# WOPR_PC.net
KiCad netlist of a schematic drawn in Altium Designer
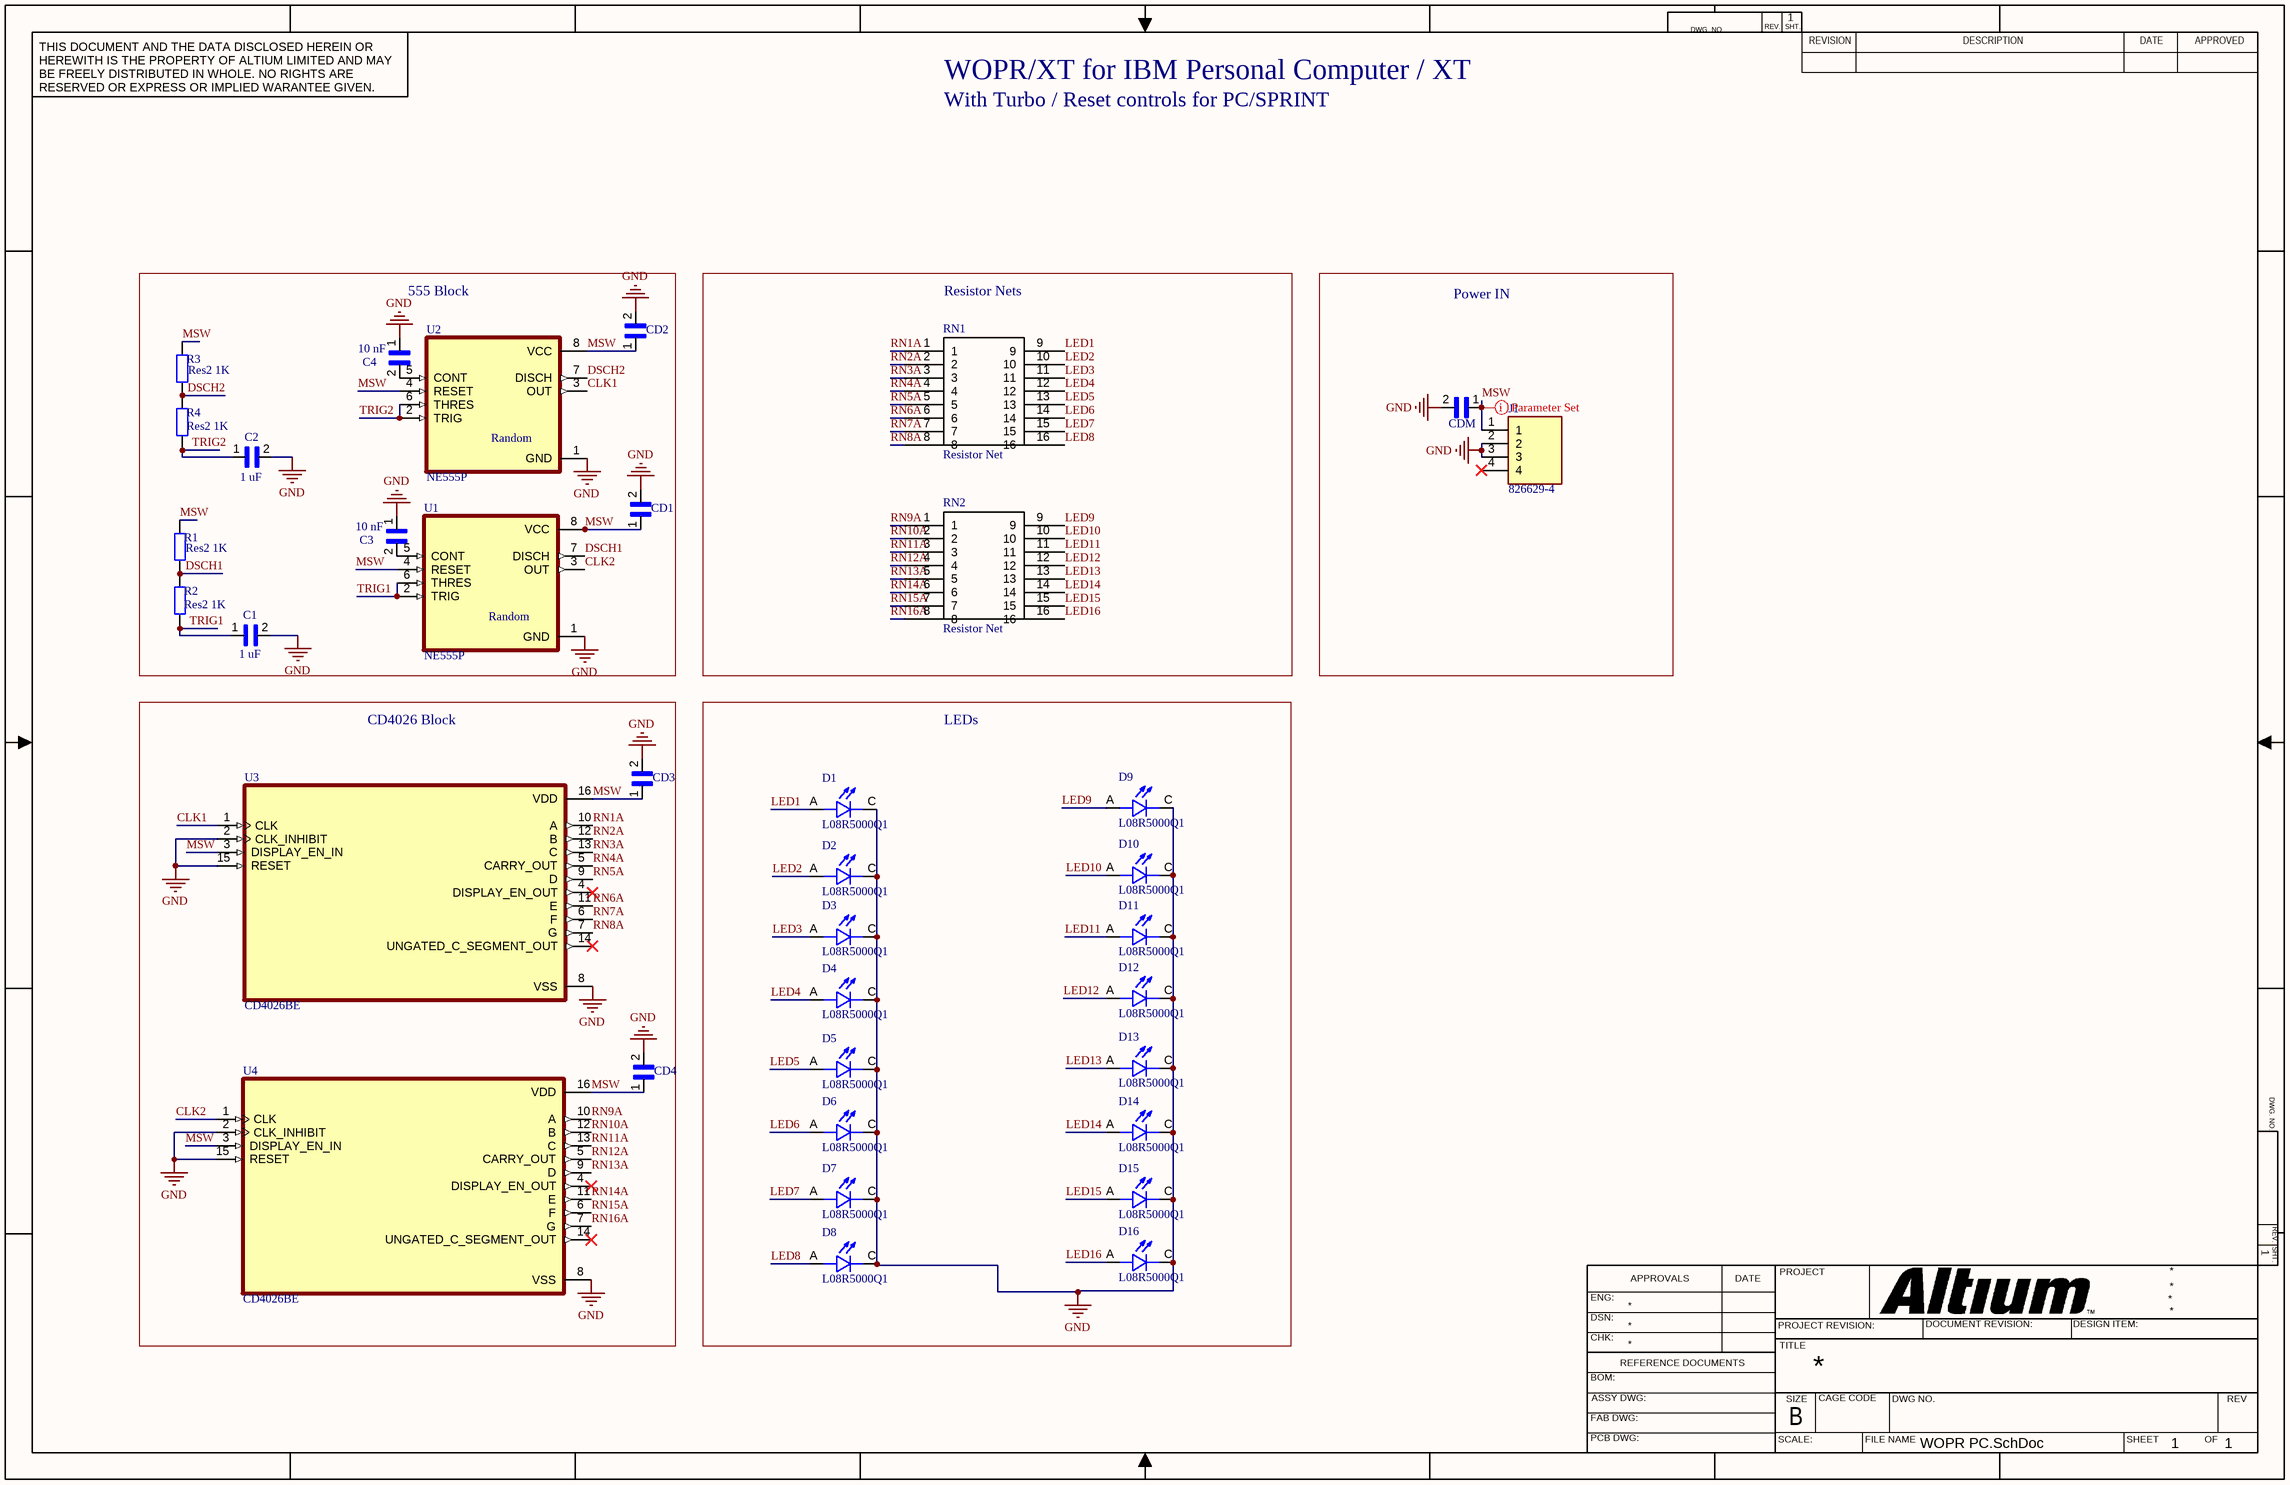
[diagram p0: WOPR PC.SchDoc]

(export (version "E")
  (design (tool "Eeschema 10.0.6"))
  (components
    (comp (ref "C1")
      (value "1 uF")
      (footprint "CAPRB250W50L400T250H550")
      (description "COMMERCIAL GRADE, HALOGEN FREE DIPPED RADIAL / BULK")
      (fields (field (name "MP") "FG18X7R1E105KRT00") (field (name "DIGI-KEY_PART_NUMBER") "445-180204-ND"))
      (libsource (lib "FG18X7R1E105KRT00") (part "FG18X7R1E105KRT00"))
    )
    (comp (ref "C2")
      (value "1 uF")
      (footprint "CAPRB250W50L400T250H550")
      (description "COMMERCIAL GRADE, HALOGEN FREE DIPPED RADIAL / BULK")
      (fields (field (name "MP") "FG18X7R1E105KRT00") (field (name "DIGI-KEY_PART_NUMBER") "445-180204-ND"))
      (libsource (lib "FG18X7R1E105KRT00") (part "FG18X7R1E105KRT00"))
    )
    (comp (ref "C3")
      (value "10 nF")
      (footprint "CAPRB750W60L1450T500H1850")
      (description "Cap Ceramic Single 0.01uF 2000V E -20% to 80% (14.5 X 5mm) Radial Disc 7.5mm 105Â°C Bag")
      (fields (field (name "MP") "CK45E3DD103ZYGNA") (field (name "DIGI-KEY_PART_NUMBER") "445-175346-ND"))
      (libsource (lib "CK45-E3DD103ZYGNA") (part "CK45-E3DD103ZYGNA"))
    )
    (comp (ref "C4")
      (value "10 nF")
      (footprint "CAPRB750W60L1450T500H1850")
      (description "Cap Ceramic Single 0.01uF 2000V E -20% to 80% (14.5 X 5mm) Radial Disc 7.5mm 105Â°C Bag")
      (fields (field (name "MP") "CK45E3DD103ZYGNA") (field (name "DIGI-KEY_PART_NUMBER") "445-175346-ND"))
      (libsource (lib "CK45-E3DD103ZYGNA") (part "CK45-E3DD103ZYGNA"))
    )
    (comp (ref "CD1")
      (value "FG18X7R1H473KNT06")
      (footprint "CAPRB250W50L400T250H550")
      (description "COMMERCIAL GRADE, HALOGEN FREE DIPPED RADIAL / AMMO PACK")
      (fields (field (name "DIGI-KEY_PART_NUMBER") "445-173275-1-ND") (field (name "MF") "TDK"))
      (libsource (lib "FG18X7R1H473KNT06") (part "FG18X7R1H473KNT06"))
    )
    (comp (ref "CD2")
      (value "FG18X7R1H473KNT06")
      (footprint "CAPRB250W50L400T250H550")
      (description "COMMERCIAL GRADE, HALOGEN FREE DIPPED RADIAL / AMMO PACK")
      (fields (field (name "DIGI-KEY_PART_NUMBER") "445-173275-1-ND") (field (name "MF") "TDK"))
      (libsource (lib "FG18X7R1H473KNT06") (part "FG18X7R1H473KNT06"))
    )
    (comp (ref "CD3")
      (value "FG18X7R1H473KNT06")
      (footprint "CAPRB250W50L400T250H550")
      (description "COMMERCIAL GRADE, HALOGEN FREE DIPPED RADIAL / AMMO PACK")
      (fields (field (name "DIGI-KEY_PART_NUMBER") "445-173275-1-ND") (field (name "MF") "TDK"))
      (libsource (lib "FG18X7R1H473KNT06") (part "FG18X7R1H473KNT06"))
    )
    (comp (ref "CD4")
      (value "FG18X7R1H473KNT06")
      (footprint "CAPRB250W50L400T250H550")
      (description "COMMERCIAL GRADE, HALOGEN FREE DIPPED RADIAL / AMMO PACK")
      (fields (field (name "DIGI-KEY_PART_NUMBER") "445-173275-1-ND") (field (name "MF") "TDK"))
      (libsource (lib "FG18X7R1H473KNT06") (part "FG18X7R1H473KNT06"))
    )
    (comp (ref "CDM")
      (value "FG18X7R1H473KNT06")
      (footprint "CAPRB250W50L400T250H550")
      (description "COMMERCIAL GRADE, HALOGEN FREE DIPPED RADIAL / AMMO PACK")
      (fields (field (name "DIGI-KEY_PART_NUMBER") "445-173275-1-ND") (field (name "MF") "TDK"))
      (libsource (lib "") (part "FG18X7R1H473KNT06_1"))
    )
    (comp (ref "D1")
      (value "L08R5000Q1")
      (footprint "LEDRD254W57D500H1070")
      (description "LED, Orange, Through Hole, T-1 3/4 (5mm), 30 mA, 2.1 V, 635 nm")
      (libsource (lib "L08R5000Q1") (part "L08R5000Q1"))
    )
    (comp (ref "D2")
      (value "L08R5000Q1")
      (footprint "LEDRD254W57D500H1070")
      (description "LED, Orange, Through Hole, T-1 3/4 (5mm), 30 mA, 2.1 V, 635 nm")
      (libsource (lib "L08R5000Q1") (part "L08R5000Q1"))
    )
    (comp (ref "D3")
      (value "L08R5000Q1")
      (footprint "LEDRD254W57D500H1070")
      (description "LED, Orange, Through Hole, T-1 3/4 (5mm), 30 mA, 2.1 V, 635 nm")
      (libsource (lib "L08R5000Q1") (part "L08R5000Q1"))
    )
    (comp (ref "D4")
      (value "L08R5000Q1")
      (footprint "LEDRD254W57D500H1070")
      (description "LED, Orange, Through Hole, T-1 3/4 (5mm), 30 mA, 2.1 V, 635 nm")
      (libsource (lib "L08R5000Q1") (part "L08R5000Q1"))
    )
    (comp (ref "D5")
      (value "L08R5000Q1")
      (footprint "LEDRD254W57D500H1070")
      (description "LED, Orange, Through Hole, T-1 3/4 (5mm), 30 mA, 2.1 V, 635 nm")
      (libsource (lib "L08R5000Q1") (part "L08R5000Q1"))
    )
    (comp (ref "D6")
      (value "L08R5000Q1")
      (footprint "LEDRD254W57D500H1070")
      (description "LED, Orange, Through Hole, T-1 3/4 (5mm), 30 mA, 2.1 V, 635 nm")
      (libsource (lib "L08R5000Q1") (part "L08R5000Q1"))
    )
    (comp (ref "D7")
      (value "L08R5000Q1")
      (footprint "LEDRD254W57D500H1070")
      (description "LED, Orange, Through Hole, T-1 3/4 (5mm), 30 mA, 2.1 V, 635 nm")
      (libsource (lib "L08R5000Q1") (part "L08R5000Q1"))
    )
    (comp (ref "D8")
      (value "L08R5000Q1")
      (footprint "LEDRD254W57D500H1070")
      (description "LED, Orange, Through Hole, T-1 3/4 (5mm), 30 mA, 2.1 V, 635 nm")
      (libsource (lib "L08R5000Q1") (part "L08R5000Q1"))
    )
    (comp (ref "D9")
      (value "L08R5000Q1")
      (footprint "LEDRD254W57D500H1070")
      (description "LED, Orange, Through Hole, T-1 3/4 (5mm), 30 mA, 2.1 V, 635 nm")
      (libsource (lib "L08R5000Q1") (part "L08R5000Q1"))
    )
    (comp (ref "D10")
      (value "L08R5000Q1")
      (footprint "LEDRD254W57D500H1070")
      (description "LED, Orange, Through Hole, T-1 3/4 (5mm), 30 mA, 2.1 V, 635 nm")
      (libsource (lib "L08R5000Q1") (part "L08R5000Q1"))
    )
    (comp (ref "D11")
      (value "L08R5000Q1")
      (footprint "LEDRD254W57D500H1070")
      (description "LED, Orange, Through Hole, T-1 3/4 (5mm), 30 mA, 2.1 V, 635 nm")
      (libsource (lib "L08R5000Q1") (part "L08R5000Q1"))
    )
    (comp (ref "D12")
      (value "L08R5000Q1")
      (footprint "LEDRD254W57D500H1070")
      (description "LED, Orange, Through Hole, T-1 3/4 (5mm), 30 mA, 2.1 V, 635 nm")
      (libsource (lib "L08R5000Q1") (part "L08R5000Q1"))
    )
    (comp (ref "D13")
      (value "L08R5000Q1")
      (footprint "LEDRD254W57D500H1070")
      (description "LED, Orange, Through Hole, T-1 3/4 (5mm), 30 mA, 2.1 V, 635 nm")
      (libsource (lib "L08R5000Q1") (part "L08R5000Q1"))
    )
    (comp (ref "D14")
      (value "L08R5000Q1")
      (footprint "LEDRD254W57D500H1070")
      (description "LED, Orange, Through Hole, T-1 3/4 (5mm), 30 mA, 2.1 V, 635 nm")
      (libsource (lib "L08R5000Q1") (part "L08R5000Q1"))
    )
    (comp (ref "D15")
      (value "L08R5000Q1")
      (footprint "LEDRD254W57D500H1070")
      (description "LED, Orange, Through Hole, T-1 3/4 (5mm), 30 mA, 2.1 V, 635 nm")
      (libsource (lib "L08R5000Q1") (part "L08R5000Q1"))
    )
    (comp (ref "D16")
      (value "L08R5000Q1")
      (footprint "LEDRD254W57D500H1070")
      (description "LED, Orange, Through Hole, T-1 3/4 (5mm), 30 mA, 2.1 V, 635 nm")
      (libsource (lib "L08R5000Q1") (part "L08R5000Q1"))
    )
    (comp (ref "J1")
      (value "826629-4")
      (footprint "TE_826629-4")
      (description "Conn Unshrouded Header HDR 4 POS 2.54mm Solder ST Thru-Hole Automotive Carton")
      (fields (field (name "MF") "TE Connectivity"))
      (libsource (lib "826629-4") (part "826629-4"))
    )
    (comp (ref "R1")
      (value "Res2")
      (footprint "AXIAL-0.4")
      (description "Resistor")
      (fields (field (name "ALTIUM_VALUE") "1K") (field (name "PUBLISHER") "Altium Limited"))
      (libsource (lib "Miscellaneous Devices") (part "Res2"))
    )
    (comp (ref "R2")
      (value "Res2")
      (footprint "AXIAL-0.4")
      (description "Resistor")
      (fields (field (name "ALTIUM_VALUE") "1K") (field (name "PUBLISHER") "Altium Limited"))
      (libsource (lib "Miscellaneous Devices") (part "Res2"))
    )
    (comp (ref "R3")
      (value "Res2")
      (footprint "AXIAL-0.4")
      (description "Resistor")
      (fields (field (name "ALTIUM_VALUE") "1K") (field (name "PUBLISHER") "Altium Limited"))
      (libsource (lib "Miscellaneous Devices") (part "Res2"))
    )
    (comp (ref "R4")
      (value "Res2")
      (footprint "AXIAL-0.4")
      (description "Resistor")
      (fields (field (name "ALTIUM_VALUE") "1K") (field (name "PUBLISHER") "Altium Limited"))
      (libsource (lib "Miscellaneous Devices") (part "Res2"))
    )
    (comp (ref "RN1")
      (value "Resistor Net")
      (footprint "DIP794W45P254L1969H508Q16")
      (description "Resistor net, 510Ohm, 2%, 2.25W. 16Pin DIP Thru Hole. 8 Resistors.")
      (libsource (lib "4116R-1-511LF") (part "4116R-1-511LF"))
    )
    (comp (ref "RN2")
      (value "Resistor Net")
      (footprint "DIP794W45P254L1969H508Q16")
      (description "Resistor net, 510Ohm, 2%, 2.25W. 16Pin DIP Thru Hole. 8 Resistors.")
      (libsource (lib "4116R-1-511LF") (part "4116R-1-511LF"))
    )
    (comp (ref "U1")
      (value "NE555P")
      (footprint "DIP794W45P254L959H508Q8")
      (libsource (lib "NE555P") (part "NE555P"))
    )
    (comp (ref "U2")
      (value "NE555P")
      (footprint "DIP794W45P254L959H508Q8")
      (libsource (lib "NE555P") (part "NE555P"))
    )
    (comp (ref "U3")
      (value "CD4026BE")
      (footprint "DIP794W45P254L1969H508Q16")
      (fields
        (field (name "MF") "Texas Instruments")
        (field (name "BUYPART") "https://www.snapeda.com/parts/CD4026BE/Texas%20Instruments/view-part/779031/?ref=eda")
      )
      (libsource (lib "CD4026BE") (part "CD4026BE"))
    )
    (comp (ref "U4")
      (value "CD4026BE")
      (footprint "DIP794W45P254L1969H508Q16")
      (fields
        (field (name "MF") "Texas Instruments")
        (field (name "BUYPART") "https://www.snapeda.com/parts/CD4026BE/Texas%20Instruments/view-part/779031/?ref=eda")
      )
      (libsource (lib "CD4026BE") (part "CD4026BE"))
    )
  )
  (nets
    (net (code "1") (name "/CLK1") (class "Default")
      (node (ref "U2") (pin "3") (pinfunction "OUT_3") (pintype "output"))
      (node (ref "U3") (pin "1") (pinfunction "CLK_1") (pintype "input"))
    )
    (net (code "2") (name "/CLK2") (class "Default")
      (node (ref "U1") (pin "3") (pinfunction "OUT_3") (pintype "output"))
      (node (ref "U4") (pin "1") (pinfunction "CLK_1") (pintype "input"))
    )
    (net (code "3") (name "/DSCH1") (class "Default")
      (node (ref "R1") (pin "2") (pinfunction "2_2") (pintype "passive"))
      (node (ref "R2") (pin "1") (pinfunction "1_1") (pintype "passive"))
      (node (ref "U1") (pin "7") (pinfunction "DISCH_7") (pintype "output"))
    )
    (net (code "4") (name "/DSCH2") (class "Default")
      (node (ref "R3") (pin "2") (pinfunction "2_2") (pintype "passive"))
      (node (ref "R4") (pin "1") (pinfunction "1_1") (pintype "passive"))
      (node (ref "U2") (pin "7") (pinfunction "DISCH_7") (pintype "output"))
    )
    (net (code "5") (name "/LED1") (class "Default")
      (node (ref "D1") (pin "A") (pinfunction "A_A") (pintype "passive"))
      (node (ref "RN1") (pin "9") (pinfunction "9_9") (pintype "passive"))
    )
    (net (code "6") (name "/LED2") (class "Default")
      (node (ref "D2") (pin "A") (pinfunction "A_A") (pintype "passive"))
      (node (ref "RN1") (pin "10") (pinfunction "10_10") (pintype "passive"))
    )
    (net (code "7") (name "/LED3") (class "Default")
      (node (ref "D3") (pin "A") (pinfunction "A_A") (pintype "passive"))
      (node (ref "RN1") (pin "11") (pinfunction "11_11") (pintype "passive"))
    )
    (net (code "8") (name "/LED4") (class "Default")
      (node (ref "D4") (pin "A") (pinfunction "A_A") (pintype "passive"))
      (node (ref "RN1") (pin "12") (pinfunction "12_12") (pintype "passive"))
    )
    (net (code "9") (name "/LED5") (class "Default")
      (node (ref "D5") (pin "A") (pinfunction "A_A") (pintype "passive"))
      (node (ref "RN1") (pin "13") (pinfunction "13_13") (pintype "passive"))
    )
    (net (code "10") (name "/LED6") (class "Default")
      (node (ref "D6") (pin "A") (pinfunction "A_A") (pintype "passive"))
      (node (ref "RN1") (pin "14") (pinfunction "14_14") (pintype "passive"))
    )
    (net (code "11") (name "/LED7") (class "Default")
      (node (ref "D7") (pin "A") (pinfunction "A_A") (pintype "passive"))
      (node (ref "RN1") (pin "15") (pinfunction "15_15") (pintype "passive"))
    )
    (net (code "12") (name "/LED8") (class "Default")
      (node (ref "D8") (pin "A") (pinfunction "A_A") (pintype "passive"))
      (node (ref "RN1") (pin "16") (pinfunction "16_16") (pintype "passive"))
    )
    (net (code "13") (name "/LED9") (class "Default")
      (node (ref "D9") (pin "A") (pinfunction "A_A") (pintype "passive"))
      (node (ref "RN2") (pin "9") (pinfunction "9_9") (pintype "passive"))
    )
    (net (code "14") (name "/LED10") (class "Default")
      (node (ref "D10") (pin "A") (pinfunction "A_A") (pintype "passive"))
      (node (ref "RN2") (pin "10") (pinfunction "10_10") (pintype "passive"))
    )
    (net (code "15") (name "/LED11") (class "Default")
      (node (ref "D11") (pin "A") (pinfunction "A_A") (pintype "passive"))
      (node (ref "RN2") (pin "11") (pinfunction "11_11") (pintype "passive"))
    )
    (net (code "16") (name "/LED12") (class "Default")
      (node (ref "D12") (pin "A") (pinfunction "A_A") (pintype "passive"))
      (node (ref "RN2") (pin "12") (pinfunction "12_12") (pintype "passive"))
    )
    (net (code "17") (name "/LED13") (class "Default")
      (node (ref "D13") (pin "A") (pinfunction "A_A") (pintype "passive"))
      (node (ref "RN2") (pin "13") (pinfunction "13_13") (pintype "passive"))
    )
    (net (code "18") (name "/LED14") (class "Default")
      (node (ref "D14") (pin "A") (pinfunction "A_A") (pintype "passive"))
      (node (ref "RN2") (pin "14") (pinfunction "14_14") (pintype "passive"))
    )
    (net (code "19") (name "/LED15") (class "Default")
      (node (ref "D15") (pin "A") (pinfunction "A_A") (pintype "passive"))
      (node (ref "RN2") (pin "15") (pinfunction "15_15") (pintype "passive"))
    )
    (net (code "20") (name "/LED16") (class "Default")
      (node (ref "D16") (pin "A") (pinfunction "A_A") (pintype "passive"))
      (node (ref "RN2") (pin "16") (pinfunction "16_16") (pintype "passive"))
    )
    (net (code "21") (name "/MSW") (class "Default")
      (node (ref "CD1") (pin "1") (pinfunction "1_1") (pintype "passive"))
      (node (ref "CD2") (pin "1") (pinfunction "1_1") (pintype "passive"))
      (node (ref "CD3") (pin "1") (pinfunction "1_1") (pintype "passive"))
      (node (ref "CD4") (pin "1") (pinfunction "1_1") (pintype "passive"))
      (node (ref "CDM") (pin "1") (pinfunction "1_1") (pintype "passive"))
      (node (ref "J1") (pin "1") (pinfunction "1_1") (pintype "passive"))
      (node (ref "R1") (pin "1") (pinfunction "1_1") (pintype "passive"))
      (node (ref "R3") (pin "1") (pinfunction "1_1") (pintype "passive"))
      (node (ref "U1") (pin "4") (pinfunction "RESET_4") (pintype "input"))
      (node (ref "U1") (pin "8") (pinfunction "VCC_8") (pintype "power_in"))
      (node (ref "U2") (pin "4") (pinfunction "RESET_4") (pintype "input"))
      (node (ref "U2") (pin "8") (pinfunction "VCC_8") (pintype "power_in"))
      (node (ref "U3") (pin "16") (pinfunction "VDD_16") (pintype "power_in"))
      (node (ref "U3") (pin "3") (pinfunction "DISPLAY_EN_IN_3") (pintype "input"))
      (node (ref "U4") (pin "16") (pinfunction "VDD_16") (pintype "power_in"))
      (node (ref "U4") (pin "3") (pinfunction "DISPLAY_EN_IN_3") (pintype "input"))
    )
    (net (code "22") (name "/RN1A") (class "Default")
      (node (ref "RN1") (pin "1") (pinfunction "1_1") (pintype "passive"))
      (node (ref "U3") (pin "10") (pinfunction "A_10") (pintype "output"))
    )
    (net (code "23") (name "/RN2A") (class "Default")
      (node (ref "RN1") (pin "2") (pinfunction "2_2") (pintype "passive"))
      (node (ref "U3") (pin "12") (pinfunction "B_12") (pintype "output"))
    )
    (net (code "24") (name "/RN3A") (class "Default")
      (node (ref "RN1") (pin "3") (pinfunction "3_3") (pintype "passive"))
      (node (ref "U3") (pin "13") (pinfunction "C_13") (pintype "output"))
    )
    (net (code "25") (name "/RN4A") (class "Default")
      (node (ref "RN1") (pin "4") (pinfunction "4_4") (pintype "passive"))
      (node (ref "U3") (pin "5") (pinfunction "CARRY_OUT_5") (pintype "output"))
    )
    (net (code "26") (name "/RN5A") (class "Default")
      (node (ref "RN1") (pin "5") (pinfunction "5_5") (pintype "passive"))
      (node (ref "U3") (pin "9") (pinfunction "D_9") (pintype "output"))
    )
    (net (code "27") (name "/RN6A") (class "Default")
      (node (ref "RN1") (pin "6") (pinfunction "6_6") (pintype "passive"))
      (node (ref "U3") (pin "11") (pinfunction "E_11") (pintype "output"))
    )
    (net (code "28") (name "/RN7A") (class "Default")
      (node (ref "RN1") (pin "7") (pinfunction "7_7") (pintype "passive"))
      (node (ref "U3") (pin "6") (pinfunction "F_6") (pintype "output"))
    )
    (net (code "29") (name "/RN8A") (class "Default")
      (node (ref "RN1") (pin "8") (pinfunction "8_8") (pintype "passive"))
      (node (ref "U3") (pin "7") (pinfunction "G_7") (pintype "output"))
    )
    (net (code "30") (name "/RN9A") (class "Default")
      (node (ref "RN2") (pin "1") (pinfunction "1_1") (pintype "passive"))
      (node (ref "U4") (pin "10") (pinfunction "A_10") (pintype "output"))
    )
    (net (code "31") (name "/RN10A") (class "Default")
      (node (ref "RN2") (pin "2") (pinfunction "2_2") (pintype "passive"))
      (node (ref "U4") (pin "12") (pinfunction "B_12") (pintype "output"))
    )
    (net (code "32") (name "/RN11A") (class "Default")
      (node (ref "RN2") (pin "3") (pinfunction "3_3") (pintype "passive"))
      (node (ref "U4") (pin "13") (pinfunction "C_13") (pintype "output"))
    )
    (net (code "33") (name "/RN12A") (class "Default")
      (node (ref "RN2") (pin "4") (pinfunction "4_4") (pintype "passive"))
      (node (ref "U4") (pin "5") (pinfunction "CARRY_OUT_5") (pintype "output"))
    )
    (net (code "34") (name "/RN13A") (class "Default")
      (node (ref "RN2") (pin "5") (pinfunction "5_5") (pintype "passive"))
      (node (ref "U4") (pin "9") (pinfunction "D_9") (pintype "output"))
    )
    (net (code "35") (name "/RN14A") (class "Default")
      (node (ref "RN2") (pin "6") (pinfunction "6_6") (pintype "passive"))
      (node (ref "U4") (pin "11") (pinfunction "E_11") (pintype "output"))
    )
    (net (code "36") (name "/RN15A") (class "Default")
      (node (ref "RN2") (pin "7") (pinfunction "7_7") (pintype "passive"))
      (node (ref "U4") (pin "6") (pinfunction "F_6") (pintype "output"))
    )
    (net (code "37") (name "/RN16A") (class "Default")
      (node (ref "RN2") (pin "8") (pinfunction "8_8") (pintype "passive"))
      (node (ref "U4") (pin "7") (pinfunction "G_7") (pintype "output"))
    )
    (net (code "38") (name "/TRIG1") (class "Default")
      (node (ref "C1") (pin "1") (pinfunction "1_1") (pintype "passive"))
      (node (ref "R2") (pin "2") (pinfunction "2_2") (pintype "passive"))
      (node (ref "U1") (pin "2") (pinfunction "TRIG_2") (pintype "input"))
      (node (ref "U1") (pin "6") (pinfunction "THRES_6") (pintype "input"))
    )
    (net (code "39") (name "/TRIG2") (class "Default")
      (node (ref "C2") (pin "1") (pinfunction "1_1") (pintype "passive"))
      (node (ref "R4") (pin "2") (pinfunction "2_2") (pintype "passive"))
      (node (ref "U2") (pin "2") (pinfunction "TRIG_2") (pintype "input"))
      (node (ref "U2") (pin "6") (pinfunction "THRES_6") (pintype "input"))
    )
    (net (code "40") (name "GND") (class "Default")
      (node (ref "C1") (pin "2") (pinfunction "2_2") (pintype "passive"))
      (node (ref "C2") (pin "2") (pinfunction "2_2") (pintype "passive"))
      (node (ref "C3") (pin "1") (pinfunction "1_1") (pintype "passive"))
      (node (ref "C4") (pin "1") (pinfunction "1_1") (pintype "passive"))
      (node (ref "CD1") (pin "2") (pinfunction "2_2") (pintype "passive"))
      (node (ref "CD2") (pin "2") (pinfunction "2_2") (pintype "passive"))
      (node (ref "CD3") (pin "2") (pinfunction "2_2") (pintype "passive"))
      (node (ref "CD4") (pin "2") (pinfunction "2_2") (pintype "passive"))
      (node (ref "CDM") (pin "2") (pinfunction "2_2") (pintype "passive"))
      (node (ref "D1") (pin "C") (pinfunction "C_C") (pintype "passive"))
      (node (ref "D10") (pin "C") (pinfunction "C_C") (pintype "passive"))
      (node (ref "D11") (pin "C") (pinfunction "C_C") (pintype "passive"))
      (node (ref "D12") (pin "C") (pinfunction "C_C") (pintype "passive"))
      (node (ref "D13") (pin "C") (pinfunction "C_C") (pintype "passive"))
      (node (ref "D14") (pin "C") (pinfunction "C_C") (pintype "passive"))
      (node (ref "D15") (pin "C") (pinfunction "C_C") (pintype "passive"))
      (node (ref "D16") (pin "C") (pinfunction "C_C") (pintype "passive"))
      (node (ref "D2") (pin "C") (pinfunction "C_C") (pintype "passive"))
      (node (ref "D3") (pin "C") (pinfunction "C_C") (pintype "passive"))
      (node (ref "D4") (pin "C") (pinfunction "C_C") (pintype "passive"))
      (node (ref "D5") (pin "C") (pinfunction "C_C") (pintype "passive"))
      (node (ref "D6") (pin "C") (pinfunction "C_C") (pintype "passive"))
      (node (ref "D7") (pin "C") (pinfunction "C_C") (pintype "passive"))
      (node (ref "D8") (pin "C") (pinfunction "C_C") (pintype "passive"))
      (node (ref "D9") (pin "C") (pinfunction "C_C") (pintype "passive"))
      (node (ref "J1") (pin "2") (pinfunction "2_2") (pintype "passive"))
      (node (ref "J1") (pin "3") (pinfunction "3_3") (pintype "passive"))
      (node (ref "U1") (pin "1") (pinfunction "GND_1") (pintype "power_in"))
      (node (ref "U2") (pin "1") (pinfunction "GND_1") (pintype "power_in"))
      (node (ref "U3") (pin "15") (pinfunction "RESET_15") (pintype "input"))
      (node (ref "U3") (pin "2") (pinfunction "CLK_INHIBIT_2") (pintype "input"))
      (node (ref "U3") (pin "8") (pinfunction "VSS_8") (pintype "power_in"))
      (node (ref "U4") (pin "15") (pinfunction "RESET_15") (pintype "input"))
      (node (ref "U4") (pin "2") (pinfunction "CLK_INHIBIT_2") (pintype "input"))
      (node (ref "U4") (pin "8") (pinfunction "VSS_8") (pintype "power_in"))
    )
    (net (code "41") (name "Net-(U1-CONT)") (class "Default")
      (node (ref "C3") (pin "2") (pinfunction "2_2") (pintype "passive"))
      (node (ref "U1") (pin "5") (pinfunction "CONT_5") (pintype "input"))
    )
    (net (code "42") (name "Net-(U2-CONT)") (class "Default")
      (node (ref "C4") (pin "2") (pinfunction "2_2") (pintype "passive"))
      (node (ref "U2") (pin "5") (pinfunction "CONT_5") (pintype "input"))
    )
    (net (code "43") (name "unconnected-(J1-Pad4)") (class "Default")
      (node (ref "J1") (pin "4") (pinfunction "4_4") (pintype "passive+no_connect"))
    )
    (net (code "44") (name "unconnected-(U3-DISPLAY_EN_OUT-Pad4)") (class "Default")
      (node (ref "U3") (pin "4") (pinfunction "DISPLAY_EN_OUT_4") (pintype "output+no_connect"))
    )
    (net (code "45") (name "unconnected-(U3-UNGATED_C_SEGMENT_OUT-Pad14)") (class "Default")
      (node (ref "U3") (pin "14") (pinfunction "UNGATED_C_SEGMENT_OUT_14") (pintype "output+no_connect"))
    )
    (net (code "46") (name "unconnected-(U4-DISPLAY_EN_OUT-Pad4)") (class "Default")
      (node (ref "U4") (pin "4") (pinfunction "DISPLAY_EN_OUT_4") (pintype "output+no_connect"))
    )
    (net (code "47") (name "unconnected-(U4-UNGATED_C_SEGMENT_OUT-Pad14)") (class "Default")
      (node (ref "U4") (pin "14") (pinfunction "UNGATED_C_SEGMENT_OUT_14") (pintype "output+no_connect"))
    )
  )
)
